# turntable_final.net
KiCad netlist of a schematic drawn in EAGLE
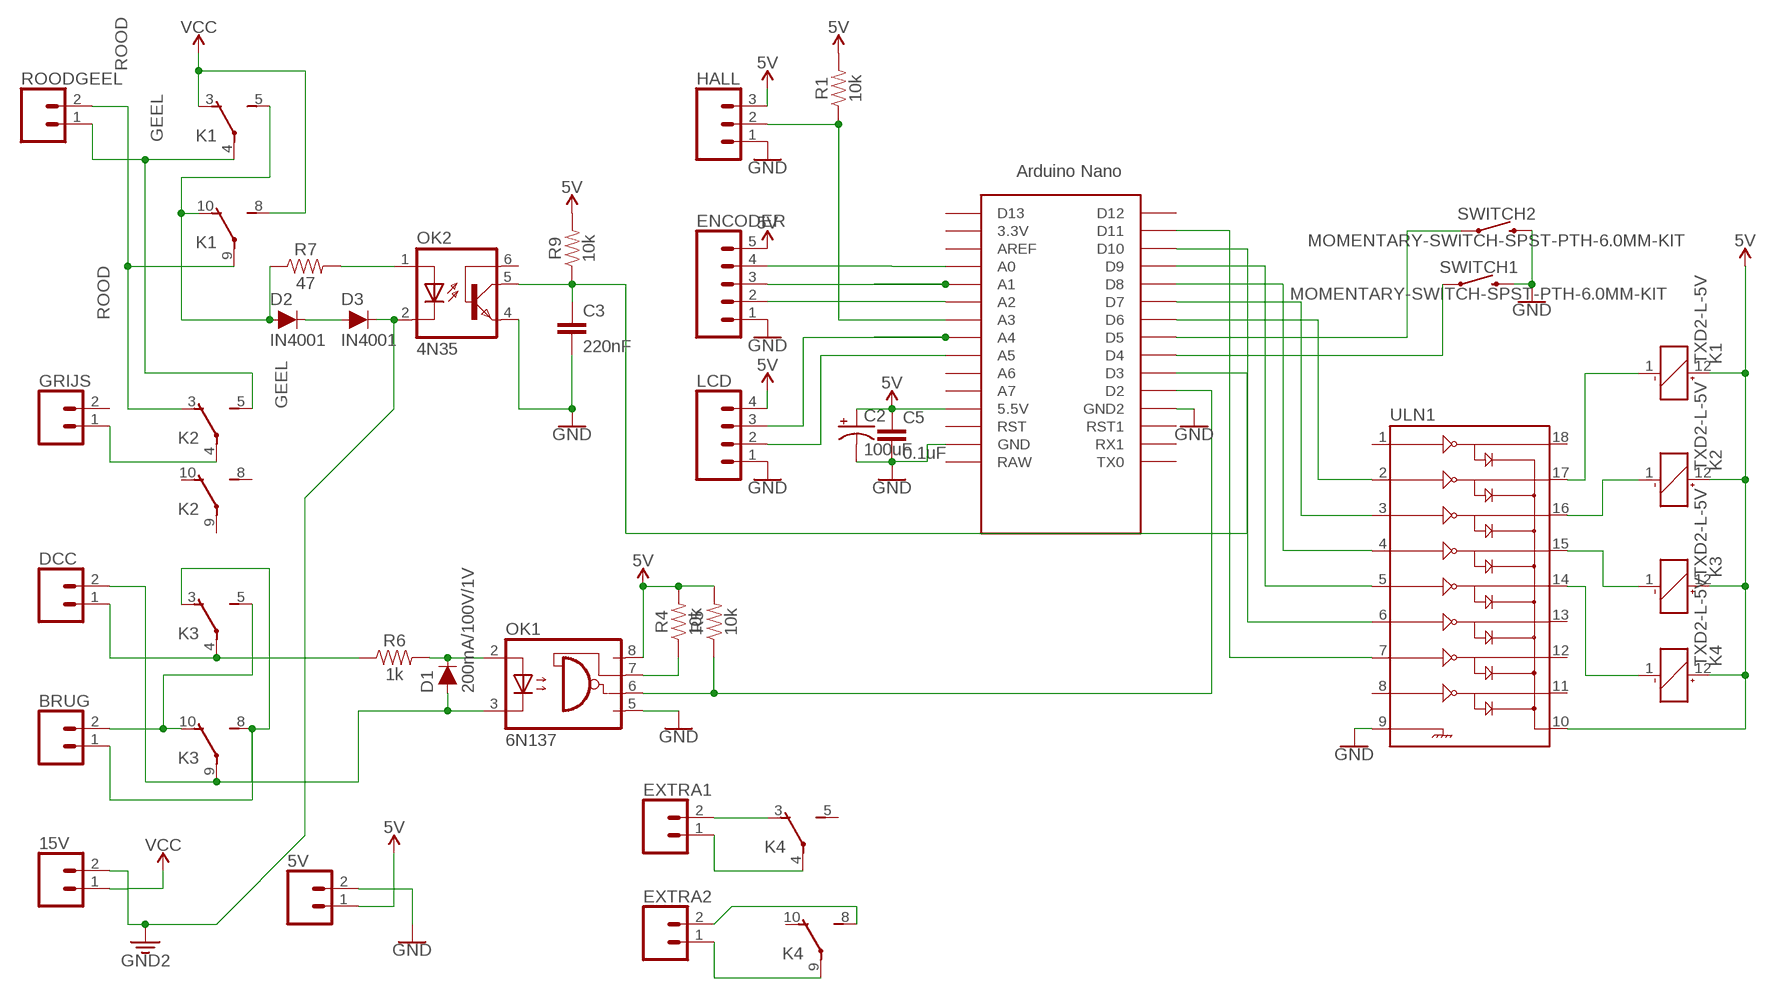
[diagram p0: schematic, sheet 1]

(export (version "E")
  (design (tool "Eeschema 10.0.6"))
  (components
    (comp (ref "5V")
      (value "CONN_023.5MM_LOCK")
      (footprint "eagle-import:SCREWTERMINAL-3.5MM-2_LOCK")
      (libsource (lib "eagle-import") (part "CONN_023.5MM_LOCK"))
    )
    (comp (ref "15V")
      (value "CONN_023.5MM_LOCK")
      (footprint "eagle-import:SCREWTERMINAL-3.5MM-2_LOCK")
      (libsource (lib "eagle-import") (part "CONN_023.5MM_LOCK"))
    )
    (comp (ref "BRUG")
      (value "CONN_023.5MM_LOCK")
      (footprint "eagle-import:SCREWTERMINAL-3.5MM-2_LOCK")
      (libsource (lib "eagle-import") (part "CONN_023.5MM_LOCK"))
    )
    (comp (ref "C2")
      (value "100uF")
      (footprint "eagle-import:CPOL-RADIAL-2.5MM-5MM")
      (libsource (lib "eagle-import") (part "10UF-POLAR-RADIAL-2.5MM-25V-20%"))
    )
    (comp (ref "C3")
      (value "220nF")
      (footprint "eagle-import:CAP-PTH-SMALL-KIT")
      (libsource (lib "eagle-import") (part "0.1UF-KIT-EZ-50V-20%"))
    )
    (comp (ref "C5")
      (value "0.1uF")
      (footprint "eagle-import:CAP-PTH-SMALL-KIT")
      (libsource (lib "eagle-import") (part "0.1UF-KIT-EZ-50V-20%"))
    )
    (comp (ref "D1")
      (value "200mA/100V/1V")
      (footprint "eagle-import:DIODE-1N4148")
      (libsource (lib "eagle-import") (part "DIODE-1N4148"))
    )
    (comp (ref "D2")
      (value "IN4001")
      (footprint "eagle-import:DIODE-1N4001")
      (libsource (lib "eagle-import") (part "DIODE-PTH"))
    )
    (comp (ref "D3")
      (value "IN4001")
      (footprint "eagle-import:DIODE-1N4001")
      (libsource (lib "eagle-import") (part "DIODE-PTH"))
    )
    (comp (ref "DCC")
      (value "CONN_023.5MM_LOCK")
      (footprint "eagle-import:SCREWTERMINAL-3.5MM-2_LOCK")
      (libsource (lib "eagle-import") (part "CONN_023.5MM_LOCK"))
    )
    (comp (ref "ENCODER")
      (value "CONN_05")
      (footprint "eagle-import:1X05")
      (libsource (lib "eagle-import") (part "CONN_05"))
    )
    (comp (ref "EXTRA1")
      (value "CONN_023.5MM_LOCK")
      (footprint "eagle-import:SCREWTERMINAL-3.5MM-2_LOCK")
      (libsource (lib "eagle-import") (part "CONN_023.5MM_LOCK"))
    )
    (comp (ref "EXTRA2")
      (value "CONN_023.5MM_LOCK")
      (footprint "eagle-import:SCREWTERMINAL-3.5MM-2_LOCK")
      (libsource (lib "eagle-import") (part "CONN_023.5MM_LOCK"))
    )
    (comp (ref "GRIJS")
      (value "CONN_023.5MM_LOCK")
      (footprint "eagle-import:SCREWTERMINAL-3.5MM-2_LOCK")
      (libsource (lib "eagle-import") (part "CONN_023.5MM_LOCK"))
    )
    (comp (ref "HALL")
      (value "CONN_03")
      (footprint "eagle-import:1X03")
      (libsource (lib "eagle-import") (part "CONN_03"))
    )
    (comp (ref "K1")
      (value "TXD2-L-5V")
      (footprint "eagle-import:TXD2")
      (libsource (lib "eagle-import") (part "TX?-D2-L5V"))
    )
    (comp (ref "K2")
      (value "TXD2-L-5V")
      (footprint "eagle-import:TXD2")
      (libsource (lib "eagle-import") (part "TX?-D2-L5V"))
    )
    (comp (ref "K3")
      (value "TXD2-L-5V")
      (footprint "eagle-import:TXD2")
      (libsource (lib "eagle-import") (part "TX?-D2-L5V"))
    )
    (comp (ref "K4")
      (value "TXD2-L-5V")
      (footprint "eagle-import:TXD2")
      (libsource (lib "eagle-import") (part "TX?-D2-L5V"))
    )
    (comp (ref "LCD")
      (value "CONN_04")
      (footprint "eagle-import:1X04")
      (libsource (lib "eagle-import") (part "CONN_04"))
    )
    (comp (ref "OK1")
      (value "6N137")
      (footprint "eagle-import:DIL08")
      (libsource (lib "eagle-import") (part "6N137"))
    )
    (comp (ref "OK2")
      (value "4N35")
      (footprint "eagle-import:DIL06")
      (fields (field (name "MF") "FAIRCHILD SEMICONDUCTOR"))
      (libsource (lib "eagle-import") (part "4N35"))
    )
    (comp (ref "R1")
      (value "10k")
      (footprint "eagle-import:AXIAL-0.3")
      (libsource (lib "eagle-import") (part "10KOHM-HORIZ-1/4W-1%"))
    )
    (comp (ref "R4")
      (value "10k")
      (footprint "eagle-import:AXIAL-0.3")
      (libsource (lib "eagle-import") (part "10KOHM-HORIZ-1/4W-1%"))
    )
    (comp (ref "R5")
      (value "10k")
      (footprint "eagle-import:AXIAL-0.3")
      (libsource (lib "eagle-import") (part "10KOHM-HORIZ-1/4W-1%"))
    )
    (comp (ref "R6")
      (value "1k")
      (footprint "eagle-import:AXIAL-0.3")
      (libsource (lib "eagle-import") (part "1KOHM-HORIZ-1/4W-1%"))
    )
    (comp (ref "R7")
      (value "47")
      (footprint "eagle-import:AXIAL-0.3")
      (libsource (lib "eagle-import") (part "100OHM-HORIZ-1/4W-1%"))
    )
    (comp (ref "R9")
      (value "10k")
      (footprint "eagle-import:AXIAL-0.3")
      (libsource (lib "eagle-import") (part "10KOHM-HORIZ-1/4W-1%"))
    )
    (comp (ref "ROODGEEL")
      (value "CONN_023.5MM_LOCK")
      (footprint "eagle-import:SCREWTERMINAL-3.5MM-2_LOCK")
      (libsource (lib "eagle-import") (part "CONN_023.5MM_LOCK"))
    )
    (comp (ref "SWITCH1")
      (value "MOMENTARY-SWITCH-SPST-PTH-6.0MM-KIT")
      (footprint "eagle-import:TACTILE_SWITCH_PTH_6.0MM_KIT")
      (libsource (lib "eagle-import") (part "MOMENTARY-SWITCH-SPST-PTH-6.0MM-KIT"))
    )
    (comp (ref "SWITCH2")
      (value "MOMENTARY-SWITCH-SPST-PTH-6.0MM-KIT")
      (footprint "eagle-import:TACTILE_SWITCH_PTH_6.0MM_KIT")
      (libsource (lib "eagle-import") (part "MOMENTARY-SWITCH-SPST-PTH-6.0MM-KIT"))
    )
    (comp (ref "U$1")
      (value "NANO")
      (footprint "eagle-import:NANO")
      (libsource (lib "eagle-import") (part "NANO"))
    )
    (comp (ref "ULN1")
      (value "ULN2803DIP")
      (footprint "eagle-import:DIL18")
      (libsource (lib "eagle-import") (part "ULN2803DIP"))
    )
  )
  (nets
    (net (code "1") (name "/GEEL") (class "Default")
      (node (ref "K1") (pin "4") (pinfunction "P_4") (pintype "passive"))
      (node (ref "K2") (pin "5") (pinfunction "S_5") (pintype "passive"))
      (node (ref "ROODGEEL") (pin "1") (pinfunction "1_1") (pintype "passive"))
    )
    (net (code "2") (name "/ROOD") (class "Default")
      (node (ref "K1") (pin "9") (pinfunction "P_9") (pintype "passive"))
      (node (ref "K2") (pin "3") (pinfunction "O_3") (pintype "passive"))
      (node (ref "ROODGEEL") (pin "2") (pinfunction "2_2") (pintype "passive"))
    )
    (net (code "3") (name "5V") (class "Default")
      (node (ref "5V") (pin "1") (pinfunction "1_1") (pintype "passive"))
      (node (ref "C2") (pin "1") (pinfunction "+_1") (pintype "passive"))
      (node (ref "C5") (pin "1") (pinfunction "1_1") (pintype "passive"))
      (node (ref "ENCODER") (pin "5") (pinfunction "5_5") (pintype "passive"))
      (node (ref "HALL") (pin "3") (pinfunction "3_3") (pintype "passive"))
      (node (ref "K1") (pin "12") (pinfunction "+_12") (pintype "passive"))
      (node (ref "K2") (pin "12") (pinfunction "+_12") (pintype "passive"))
      (node (ref "K3") (pin "12") (pinfunction "+_12") (pintype "passive"))
      (node (ref "K4") (pin "12") (pinfunction "+_12") (pintype "passive"))
      (node (ref "LCD") (pin "4") (pinfunction "4_4") (pintype "passive"))
      (node (ref "OK1") (pin "8") (pinfunction "VCC_8") (pintype "passive"))
      (node (ref "R1") (pin "P$2") (pinfunction "2_P$2") (pintype "passive"))
      (node (ref "R4") (pin "P$2") (pinfunction "2_P$2") (pintype "passive"))
      (node (ref "R5") (pin "P$2") (pinfunction "2_P$2") (pintype "passive"))
      (node (ref "R9") (pin "P$2") (pinfunction "2_P$2") (pintype "passive"))
      (node (ref "U$1") (pin "5V") (pinfunction "5.5V_5V") (pintype "bidirectional"))
      (node (ref "ULN1") (pin "10") (pinfunction "10_10") (pintype "bidirectional"))
    )
    (net (code "4") (name "GND") (class "Default")
      (node (ref "5V") (pin "2") (pinfunction "2_2") (pintype "passive"))
      (node (ref "C2") (pin "2") (pinfunction "-_2") (pintype "passive"))
      (node (ref "C3") (pin "2") (pinfunction "2_2") (pintype "passive"))
      (node (ref "C5") (pin "2") (pinfunction "2_2") (pintype "passive"))
      (node (ref "ENCODER") (pin "1") (pinfunction "1_1") (pintype "passive"))
      (node (ref "HALL") (pin "1") (pinfunction "1_1") (pintype "passive"))
      (node (ref "LCD") (pin "1") (pinfunction "1_1") (pintype "passive"))
      (node (ref "OK1") (pin "5") (pinfunction "GND_5") (pintype "passive"))
      (node (ref "OK2") (pin "4") (pinfunction "EMI_4") (pintype "passive"))
      (node (ref "SWITCH1") (pin "3") (pinfunction "2_3") (pintype "passive"))
      (node (ref "SWITCH2") (pin "3") (pinfunction "2_3") (pintype "passive"))
      (node (ref "U$1") (pin "GND") (pinfunction "GND_GND") (pintype "bidirectional"))
      (node (ref "U$1") (pin "GND1") (pinfunction "GND2_GND1") (pintype "bidirectional"))
      (node (ref "ULN1") (pin "9") (pinfunction "9_9") (pintype "bidirectional"))
    )
    (net (code "5") (name "GND2") (class "Default")
      (node (ref "15V") (pin "2") (pinfunction "2_2") (pintype "passive"))
      (node (ref "D3") (pin "C") (pinfunction "C_C") (pintype "passive"))
      (node (ref "OK2") (pin "2") (pinfunction "C_2") (pintype "passive"))
    )
    (net (code "6") (name "Net-(D2-PadC)") (class "Default")
      (node (ref "D2") (pin "C") (pinfunction "C_C") (pintype "passive"))
      (node (ref "D3") (pin "A") (pinfunction "A_A") (pintype "passive"))
    )
    (net (code "7") (name "Net-(ENCODER-Pad2)") (class "Default")
      (node (ref "ENCODER") (pin "2") (pinfunction "2_2") (pintype "passive"))
      (node (ref "U$1") (pin "A2") (pinfunction "A2_A2") (pintype "bidirectional"))
    )
    (net (code "8") (name "Net-(ENCODER-Pad3)") (class "Default")
      (node (ref "ENCODER") (pin "3") (pinfunction "3_3") (pintype "passive"))
      (node (ref "U$1") (pin "A1") (pinfunction "A1_A1") (pintype "bidirectional"))
    )
    (net (code "9") (name "Net-(ENCODER-Pad4)") (class "Default")
      (node (ref "ENCODER") (pin "4") (pinfunction "4_4") (pintype "passive"))
      (node (ref "U$1") (pin "A0") (pinfunction "A0_A0") (pintype "bidirectional"))
    )
    (net (code "10") (name "Net-(K1A-S)") (class "Default")
      (node (ref "D2") (pin "A") (pinfunction "A_A") (pintype "passive"))
      (node (ref "K1") (pin "10") (pinfunction "O_10") (pintype "passive"))
      (node (ref "K1") (pin "5") (pinfunction "S_5") (pintype "passive"))
      (node (ref "R7") (pin "P$1") (pinfunction "1_P$1") (pintype "passive"))
    )
    (net (code "11") (name "Net-(K1C--)") (class "Default")
      (node (ref "K1") (pin "1") (pinfunction "-_1") (pintype "passive"))
      (node (ref "ULN1") (pin "17") (pinfunction "17_17") (pintype "bidirectional"))
    )
    (net (code "12") (name "Net-(K2A-P)") (class "Default")
      (node (ref "GRIJS") (pin "1") (pinfunction "1_1") (pintype "passive"))
      (node (ref "K2") (pin "4") (pinfunction "P_4") (pintype "passive"))
    )
    (net (code "13") (name "Net-(K2C--)") (class "Default")
      (node (ref "K2") (pin "1") (pinfunction "-_1") (pintype "passive"))
      (node (ref "ULN1") (pin "16") (pinfunction "16_16") (pintype "bidirectional"))
    )
    (net (code "14") (name "Net-(K3A-O)") (class "Default")
      (node (ref "BRUG") (pin "1") (pinfunction "1_1") (pintype "passive"))
      (node (ref "K3") (pin "3") (pinfunction "O_3") (pintype "passive"))
      (node (ref "K3") (pin "8") (pinfunction "S_8") (pintype "passive"))
    )
    (net (code "15") (name "Net-(K3A-P)") (class "Default")
      (node (ref "DCC") (pin "1") (pinfunction "1_1") (pintype "passive"))
      (node (ref "K3") (pin "4") (pinfunction "P_4") (pintype "passive"))
      (node (ref "R6") (pin "P$1") (pinfunction "1_P$1") (pintype "passive"))
    )
    (net (code "16") (name "Net-(K3A-S)") (class "Default")
      (node (ref "BRUG") (pin "2") (pinfunction "2_2") (pintype "passive"))
      (node (ref "K3") (pin "10") (pinfunction "O_10") (pintype "passive"))
      (node (ref "K3") (pin "5") (pinfunction "S_5") (pintype "passive"))
    )
    (net (code "17") (name "Net-(K3B-P)") (class "Default")
      (node (ref "D1") (pin "A") (pinfunction "A_A") (pintype "passive"))
      (node (ref "DCC") (pin "2") (pinfunction "2_2") (pintype "passive"))
      (node (ref "K3") (pin "9") (pinfunction "P_9") (pintype "passive"))
      (node (ref "OK1") (pin "3") (pinfunction "C_3") (pintype "passive"))
    )
    (net (code "18") (name "Net-(K3C--)") (class "Default")
      (node (ref "K3") (pin "1") (pinfunction "-_1") (pintype "passive"))
      (node (ref "ULN1") (pin "15") (pinfunction "15_15") (pintype "bidirectional"))
    )
    (net (code "19") (name "Net-(K4A-O)") (class "Default")
      (node (ref "EXTRA1") (pin "2") (pinfunction "2_2") (pintype "passive"))
      (node (ref "K4") (pin "3") (pinfunction "O_3") (pintype "passive"))
    )
    (net (code "20") (name "Net-(K4A-P)") (class "Default")
      (node (ref "EXTRA1") (pin "1") (pinfunction "1_1") (pintype "passive"))
      (node (ref "K4") (pin "4") (pinfunction "P_4") (pintype "passive"))
    )
    (net (code "21") (name "Net-(K4B-P)") (class "Default")
      (node (ref "EXTRA2") (pin "1") (pinfunction "1_1") (pintype "passive"))
      (node (ref "K4") (pin "9") (pinfunction "P_9") (pintype "passive"))
    )
    (net (code "22") (name "Net-(K4B-S)") (class "Default")
      (node (ref "EXTRA2") (pin "2") (pinfunction "2_2") (pintype "passive"))
      (node (ref "K4") (pin "8") (pinfunction "S_8") (pintype "passive"))
    )
    (net (code "23") (name "Net-(K4C--)") (class "Default")
      (node (ref "K4") (pin "1") (pinfunction "-_1") (pintype "passive"))
      (node (ref "ULN1") (pin "14") (pinfunction "14_14") (pintype "bidirectional"))
    )
    (net (code "24") (name "Net-(LCD-Pad2)") (class "Default")
      (node (ref "LCD") (pin "2") (pinfunction "2_2") (pintype "passive"))
      (node (ref "U$1") (pin "A5") (pinfunction "A5_A5") (pintype "bidirectional"))
    )
    (net (code "25") (name "Net-(LCD-Pad3)") (class "Default")
      (node (ref "LCD") (pin "3") (pinfunction "3_3") (pintype "passive"))
      (node (ref "U$1") (pin "A4") (pinfunction "A4_A4") (pintype "bidirectional"))
    )
    (net (code "26") (name "Net-(OK1-A)") (class "Default")
      (node (ref "D1") (pin "C") (pinfunction "C_C") (pintype "passive"))
      (node (ref "OK1") (pin "2") (pinfunction "A_2") (pintype "passive"))
      (node (ref "R6") (pin "P$2") (pinfunction "2_P$2") (pintype "passive"))
    )
    (net (code "27") (name "Net-(OK1-VE)") (class "Default")
      (node (ref "OK1") (pin "7") (pinfunction "VE_7") (pintype "passive"))
      (node (ref "R4") (pin "P$1") (pinfunction "1_P$1") (pintype "passive"))
    )
    (net (code "28") (name "Net-(OK1-VO)") (class "Default")
      (node (ref "OK1") (pin "6") (pinfunction "VO_6") (pintype "passive"))
      (node (ref "R5") (pin "P$1") (pinfunction "1_P$1") (pintype "passive"))
      (node (ref "U$1") (pin "D2") (pinfunction "D2_D2") (pintype "bidirectional"))
    )
    (net (code "29") (name "Net-(OK2-A)") (class "Default")
      (node (ref "OK2") (pin "1") (pinfunction "A_1") (pintype "passive"))
      (node (ref "R7") (pin "P$2") (pinfunction "2_P$2") (pintype "passive"))
    )
    (net (code "30") (name "Net-(OK2-COL)") (class "Default")
      (node (ref "C3") (pin "1") (pinfunction "1_1") (pintype "passive"))
      (node (ref "OK2") (pin "5") (pinfunction "COL_5") (pintype "passive"))
      (node (ref "R9") (pin "P$1") (pinfunction "1_P$1") (pintype "passive"))
      (node (ref "U$1") (pin "D3") (pinfunction "D3_D3") (pintype "bidirectional"))
    )
    (net (code "31") (name "Net-(R1-1)") (class "Default")
      (node (ref "HALL") (pin "2") (pinfunction "2_2") (pintype "passive"))
      (node (ref "R1") (pin "P$1") (pinfunction "1_P$1") (pintype "passive"))
      (node (ref "U$1") (pin "A3") (pinfunction "A3_A3") (pintype "bidirectional"))
    )
    (net (code "32") (name "Net-(SWITCH1-Pad1)") (class "Default")
      (node (ref "SWITCH1") (pin "1") (pinfunction "1_1") (pintype "passive"))
      (node (ref "U$1") (pin "D4") (pinfunction "D4_D4") (pintype "bidirectional"))
    )
    (net (code "33") (name "Net-(SWITCH2-Pad1)") (class "Default")
      (node (ref "SWITCH2") (pin "1") (pinfunction "1_1") (pintype "passive"))
      (node (ref "U$1") (pin "D5") (pinfunction "D5_D5") (pintype "bidirectional"))
    )
    (net (code "34") (name "Net-(U$1-PadD6)") (class "Default")
      (node (ref "U$1") (pin "D6") (pinfunction "D6_D6") (pintype "bidirectional"))
      (node (ref "ULN1") (pin "2") (pinfunction "2_2") (pintype "bidirectional"))
    )
    (net (code "35") (name "Net-(U$1-PadD7)") (class "Default")
      (node (ref "U$1") (pin "D7") (pinfunction "D7_D7") (pintype "bidirectional"))
      (node (ref "ULN1") (pin "3") (pinfunction "3_3") (pintype "bidirectional"))
    )
    (net (code "36") (name "Net-(U$1-PadD8)") (class "Default")
      (node (ref "U$1") (pin "D8") (pinfunction "D8_D8") (pintype "bidirectional"))
      (node (ref "ULN1") (pin "4") (pinfunction "4_4") (pintype "bidirectional"))
    )
    (net (code "37") (name "Net-(U$1-PadD9)") (class "Default")
      (node (ref "U$1") (pin "D9") (pinfunction "D9_D9") (pintype "bidirectional"))
      (node (ref "ULN1") (pin "5") (pinfunction "5_5") (pintype "bidirectional"))
    )
    (net (code "38") (name "Net-(U$1-PadD10)") (class "Default")
      (node (ref "U$1") (pin "D10") (pinfunction "D10_D10") (pintype "bidirectional"))
      (node (ref "ULN1") (pin "6") (pinfunction "6_6") (pintype "bidirectional"))
    )
    (net (code "39") (name "Net-(U$1-PadD11)") (class "Default")
      (node (ref "U$1") (pin "D11") (pinfunction "D11_D11") (pintype "bidirectional"))
      (node (ref "ULN1") (pin "7") (pinfunction "7_7") (pintype "bidirectional"))
    )
    (net (code "40") (name "VCC") (class "Default")
      (node (ref "15V") (pin "1") (pinfunction "1_1") (pintype "passive"))
      (node (ref "K1") (pin "3") (pinfunction "O_3") (pintype "passive"))
      (node (ref "K1") (pin "8") (pinfunction "S_8") (pintype "passive"))
    )
    (net (code "41") (name "unconnected-(GRIJS-Pad2)") (class "Default")
      (node (ref "GRIJS") (pin "2") (pinfunction "2_2") (pintype "passive"))
    )
    (net (code "42") (name "unconnected-(K2B-O-Pad10)") (class "Default")
      (node (ref "K2") (pin "10") (pinfunction "O_10") (pintype "passive"))
    )
    (net (code "43") (name "unconnected-(K2B-P-Pad9)") (class "Default")
      (node (ref "K2") (pin "9") (pinfunction "P_9") (pintype "passive"))
    )
    (net (code "44") (name "unconnected-(K2B-S-Pad8)") (class "Default")
      (node (ref "K2") (pin "8") (pinfunction "S_8") (pintype "passive"))
    )
    (net (code "45") (name "unconnected-(K4A-S-Pad5)") (class "Default")
      (node (ref "K4") (pin "5") (pinfunction "S_5") (pintype "passive"))
    )
    (net (code "46") (name "unconnected-(K4B-O-Pad10)") (class "Default")
      (node (ref "K4") (pin "10") (pinfunction "O_10") (pintype "passive"))
    )
    (net (code "47") (name "unconnected-(OK2-BAS-Pad6)") (class "Default")
      (node (ref "OK2") (pin "6") (pinfunction "BAS_6") (pintype "passive"))
    )
    (net (code "48") (name "unconnected-(U$1-Pad3.3V)") (class "Default")
      (node (ref "U$1") (pin "3.3V") (pinfunction "3.3V_3.3V") (pintype "bidirectional"))
    )
    (net (code "49") (name "unconnected-(U$1-PadA6)") (class "Default")
      (node (ref "U$1") (pin "A6") (pinfunction "A6_A6") (pintype "bidirectional"))
    )
    (net (code "50") (name "unconnected-(U$1-PadA7)") (class "Default")
      (node (ref "U$1") (pin "A7") (pinfunction "A7_A7") (pintype "bidirectional"))
    )
    (net (code "51") (name "unconnected-(U$1-PadAREF)") (class "Default")
      (node (ref "U$1") (pin "AREF") (pinfunction "AREF_AREF") (pintype "bidirectional"))
    )
    (net (code "52") (name "unconnected-(U$1-PadD12)") (class "Default")
      (node (ref "U$1") (pin "D12") (pinfunction "D12_D12") (pintype "bidirectional"))
    )
    (net (code "53") (name "unconnected-(U$1-PadD13)") (class "Default")
      (node (ref "U$1") (pin "D13") (pinfunction "D13_D13") (pintype "bidirectional"))
    )
    (net (code "54") (name "unconnected-(U$1-PadICSP1)") (class "Default")
      (node (ref "U$1") (pin "ICSP1") (pinfunction "ICSP1_ICSP1") (pintype "bidirectional"))
    )
    (net (code "55") (name "unconnected-(U$1-PadICSP2)") (class "Default")
      (node (ref "U$1") (pin "ICSP2") (pinfunction "ICSP2_ICSP2") (pintype "bidirectional"))
    )
    (net (code "56") (name "unconnected-(U$1-PadICSP3)") (class "Default")
      (node (ref "U$1") (pin "ICSP3") (pinfunction "ICSP3_ICSP3") (pintype "bidirectional"))
    )
    (net (code "57") (name "unconnected-(U$1-PadICSP4)") (class "Default")
      (node (ref "U$1") (pin "ICSP4") (pinfunction "ICSP4_ICSP4") (pintype "bidirectional"))
    )
    (net (code "58") (name "unconnected-(U$1-PadICSP5)") (class "Default")
      (node (ref "U$1") (pin "ICSP5") (pinfunction "ICSP5_ICSP5") (pintype "bidirectional"))
    )
    (net (code "59") (name "unconnected-(U$1-PadICSP6)") (class "Default")
      (node (ref "U$1") (pin "ICSP6") (pinfunction "ICSP6_ICSP6") (pintype "bidirectional"))
    )
    (net (code "60") (name "unconnected-(U$1-PadRAW)") (class "Default")
      (node (ref "U$1") (pin "RAW") (pinfunction "RAW_RAW") (pintype "bidirectional"))
    )
    (net (code "61") (name "unconnected-(U$1-PadRST)") (class "Default")
      (node (ref "U$1") (pin "RST") (pinfunction "RST_RST") (pintype "bidirectional"))
    )
    (net (code "62") (name "unconnected-(U$1-PadRST1)") (class "Default")
      (node (ref "U$1") (pin "RST1") (pinfunction "RST1_RST1") (pintype "bidirectional"))
    )
    (net (code "63") (name "unconnected-(U$1-PadRX1)") (class "Default")
      (node (ref "U$1") (pin "RX1") (pinfunction "RX1_RX1") (pintype "bidirectional"))
    )
    (net (code "64") (name "unconnected-(U$1-PadTX0)") (class "Default")
      (node (ref "U$1") (pin "TX0") (pinfunction "TX0_TX0") (pintype "bidirectional"))
    )
    (net (code "65") (name "unconnected-(ULN1-Pad1)") (class "Default")
      (node (ref "ULN1") (pin "1") (pinfunction "1_1") (pintype "bidirectional"))
    )
    (net (code "66") (name "unconnected-(ULN1-Pad8)") (class "Default")
      (node (ref "ULN1") (pin "8") (pinfunction "8_8") (pintype "bidirectional"))
    )
    (net (code "67") (name "unconnected-(ULN1-Pad11)") (class "Default")
      (node (ref "ULN1") (pin "11") (pinfunction "11_11") (pintype "bidirectional"))
    )
    (net (code "68") (name "unconnected-(ULN1-Pad12)") (class "Default")
      (node (ref "ULN1") (pin "12") (pinfunction "12_12") (pintype "bidirectional"))
    )
    (net (code "69") (name "unconnected-(ULN1-Pad13)") (class "Default")
      (node (ref "ULN1") (pin "13") (pinfunction "13_13") (pintype "bidirectional"))
    )
    (net (code "70") (name "unconnected-(ULN1-Pad18)") (class "Default")
      (node (ref "ULN1") (pin "18") (pinfunction "18_18") (pintype "bidirectional"))
    )
  )
)
